# ASL1201.net
KiCad netlist of a schematic drawn in EAGLE
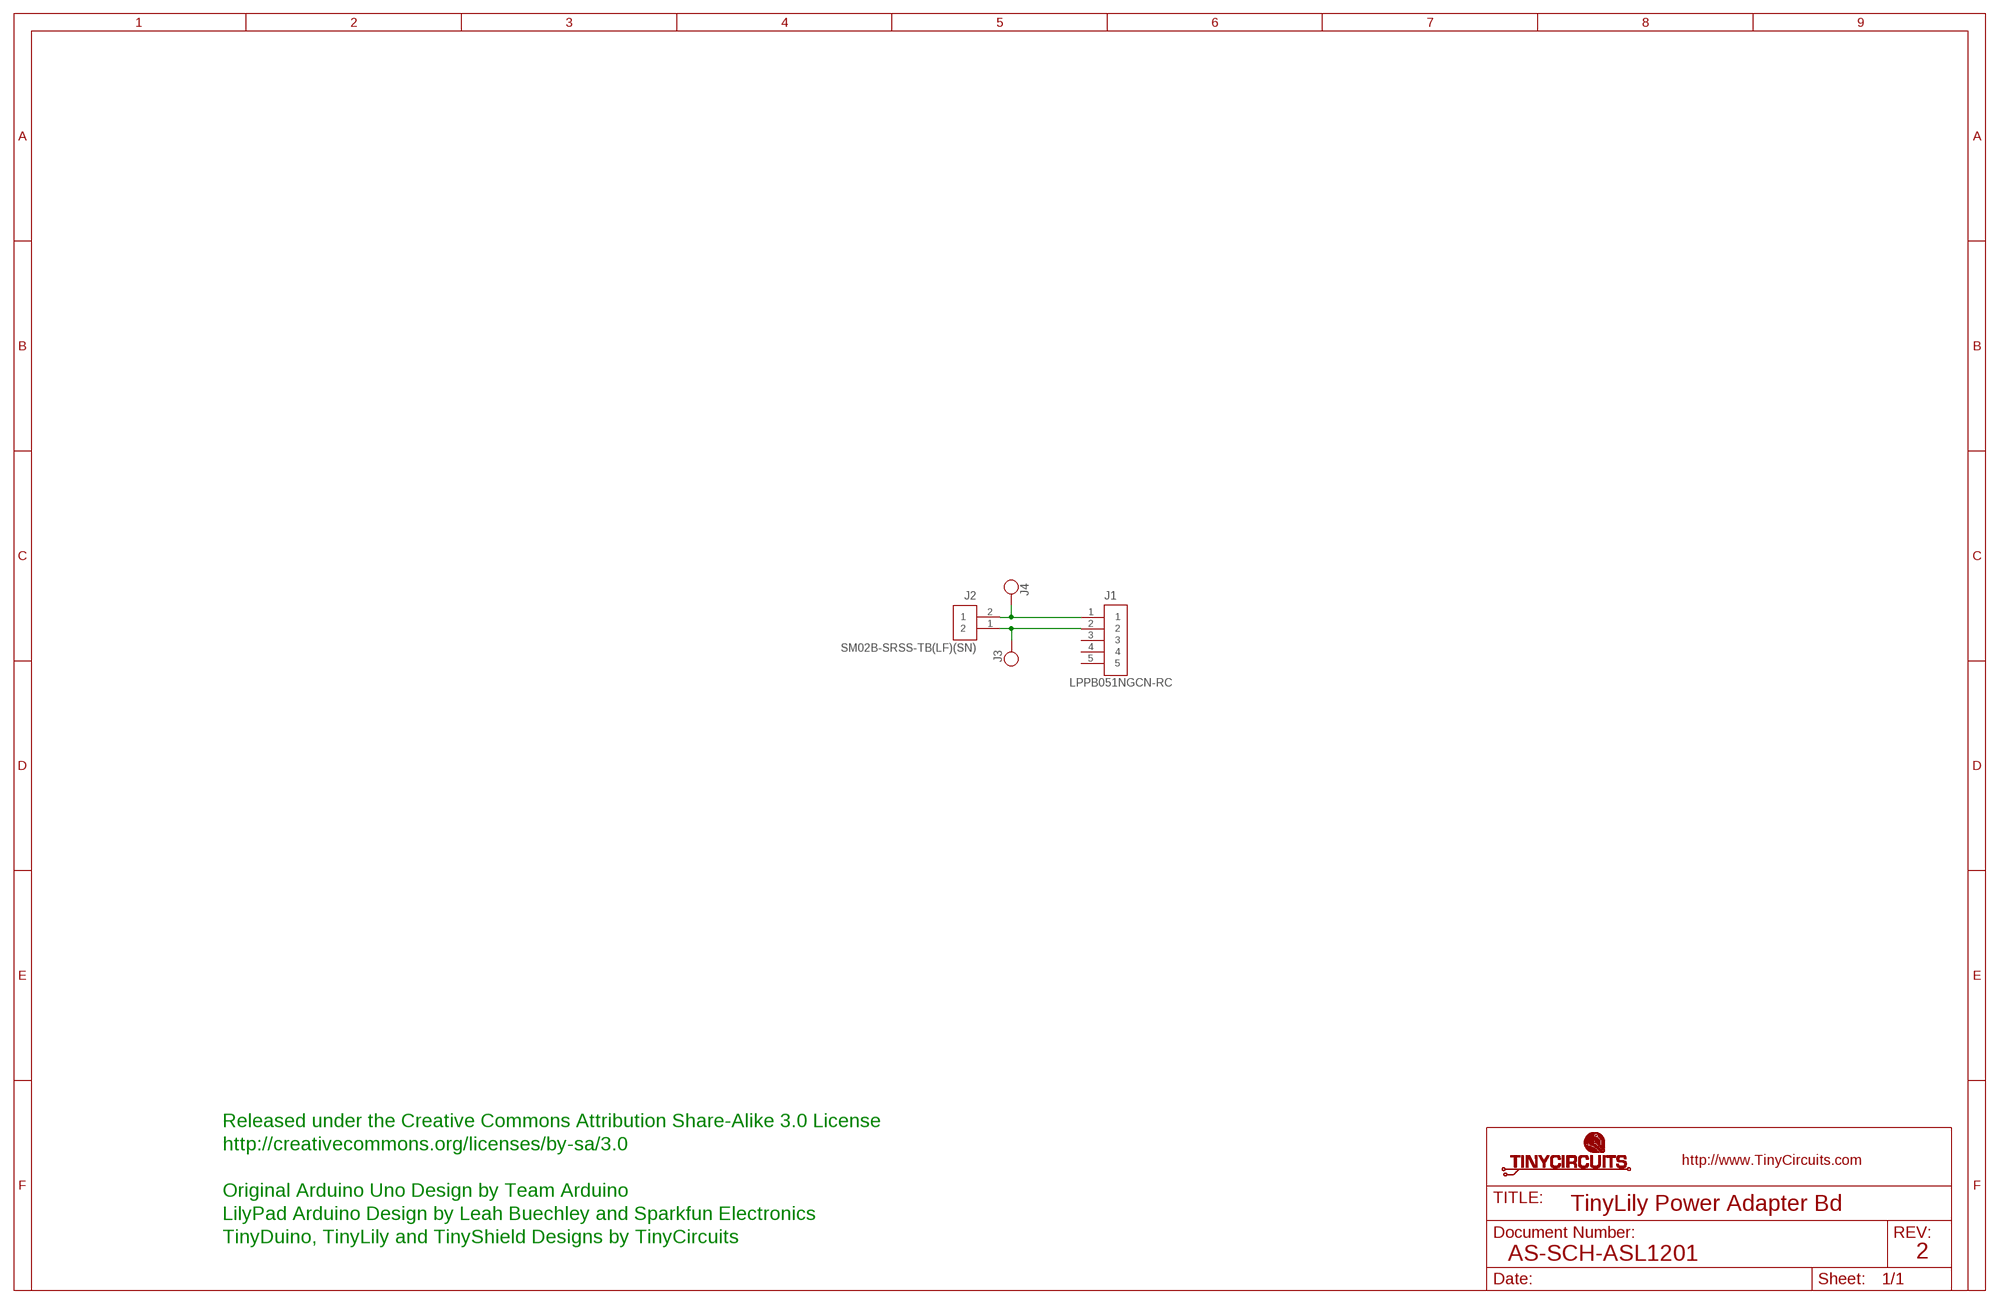
[diagram p0: schematic, sheet 1]

(export (version "E")
  (design (tool "Eeschema 10.0.6"))
  (components
    (comp (ref "J1")
      (value "LPPB051NGCN-RC")
      (footprint "eagle-import:1X5_.05_RA_TH_RECPT")
      (fields (field (name "PARTNO") "AS-ITM-00037"))
      (libsource (lib "eagle-import") (part "AS-ITM-00037"))
    )
    (comp (ref "J2")
      (value "SM02B-SRSS-TB(LF)(SN)")
      (footprint "eagle-import:JST_SH_2X1")
      (fields (field (name "PARTNO") "AS-ITM-00231"))
      (libsource (lib "eagle-import") (part "AS-ITM-00231"))
    )
    (comp (ref "J3")
      (value "PIN_1X.1\"1")
      (footprint "eagle-import:1X.1__2")
      (libsource (lib "eagle-import") (part "PIN_1X.1{dblquote}1"))
    )
    (comp (ref "J4")
      (value "PIN_1X.1\"1")
      (footprint "eagle-import:1X.1__2")
      (libsource (lib "eagle-import") (part "PIN_1X.1{dblquote}1"))
    )
  )
  (nets
    (net (code "1") (name "Net-(J2-1)") (class "Default")
      (node (ref "J1") (pin "1") (pinfunction "1_1") (pintype "bidirectional"))
      (node (ref "J2") (pin "2") (pinfunction "1_2") (pintype "bidirectional"))
      (node (ref "J4") (pin "1") (pinfunction "1_1") (pintype "bidirectional"))
    )
    (net (code "2") (name "Net-(J2-2)") (class "Default")
      (node (ref "J1") (pin "2") (pinfunction "2_2") (pintype "bidirectional"))
      (node (ref "J2") (pin "1") (pinfunction "2_1") (pintype "bidirectional"))
      (node (ref "J3") (pin "1") (pinfunction "1_1") (pintype "bidirectional"))
    )
    (net (code "3") (name "unconnected-(J1-Pad3)") (class "Default")
      (node (ref "J1") (pin "3") (pinfunction "3_3") (pintype "bidirectional"))
    )
    (net (code "4") (name "unconnected-(J1-Pad4)") (class "Default")
      (node (ref "J1") (pin "4") (pinfunction "4_4") (pintype "bidirectional"))
    )
    (net (code "5") (name "unconnected-(J1-Pad5)") (class "Default")
      (node (ref "J1") (pin "5") (pinfunction "5_5") (pintype "bidirectional"))
    )
  )
)
